# ZS-007.net
KiCad netlist of a schematic drawn in Altium Designer
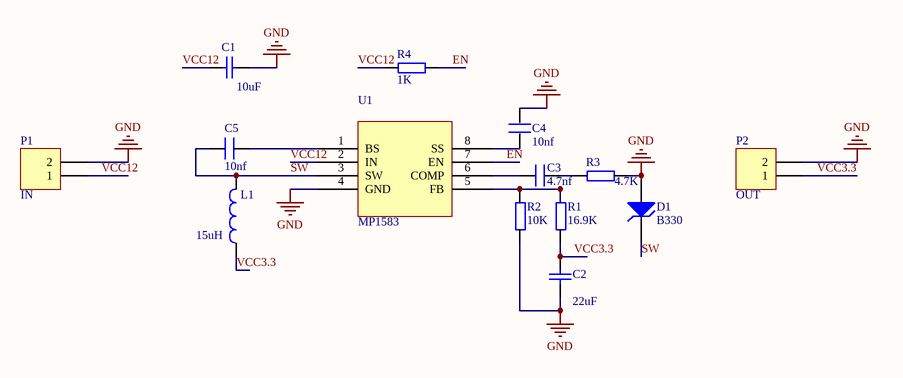
[diagram p0: ZS-007.SchDoc]

(export (version "E")
  (design (tool "Eeschema 10.0.6"))
  (components
    (comp (ref "C1")
      (value "10uF")
      (footprint "c0805")
      (description "Capacitor")
      (fields (field (name "Comment") "Cap") (field (name "PUBLISHER") "Altium Limited"))
      (libsource (lib "neoxin") (part "Cap0805"))
    )
    (comp (ref "C2")
      (value "22uF")
      (footprint "C0805")
      (description "Capacitor")
      (fields (field (name "Comment") "Cap") (field (name "PUBLISHER") "Altium Limited"))
      (libsource (lib "neoxin") (part "Cap0805"))
    )
    (comp (ref "C3") (value "4.7nf") (footprint "C0603") (libsource (lib "neoxin") (part "C")))
    (comp (ref "C4") (value "10nf") (footprint "C0603") (libsource (lib "neoxin") (part "C")))
    (comp (ref "C5") (value "10nf") (footprint "C0603") (libsource (lib "neoxin") (part "C")))
    (comp (ref "D1")
      (value "B330")
      (footprint "smb do214aa")
      (description "Zener Diode")
      (fields (field (name "PUBLISHER") "Altium Limited"))
      (libsource (lib "neoxin") (part "D Zener"))
    )
    (comp (ref "L1")
      (value "15uH")
      (footprint "15uh")
      (description "Inductor")
      (fields (field (name "PUBLISHER") "Altium Limited"))
      (libsource (lib "neoxin") (part "Inductor"))
    )
    (comp (ref "P1")
      (value "IN")
      (footprint "HDR1X2")
      (description "Header, 2-Pin")
      (fields (field (name "PUBLISHER") "Altium Limited"))
      (libsource (lib "Miscellaneous Connectors") (part "Header 2"))
    )
    (comp (ref "P2")
      (value "OUT")
      (footprint "HDR1X2")
      (description "Header, 2-Pin")
      (fields (field (name "PUBLISHER") "Altium Limited"))
      (libsource (lib "Miscellaneous Connectors") (part "Header 2"))
    )
    (comp (ref "R1") (value "16.9K") (footprint "R0603") (libsource (lib "neoxin") (part "R")))
    (comp (ref "R2") (value "10K") (footprint "R0603") (libsource (lib "neoxin") (part "R")))
    (comp (ref "R3") (value "4.7K") (footprint "R0603") (libsource (lib "neoxin") (part "R")))
    (comp (ref "R4") (value "1K") (footprint "R0603") (libsource (lib "neoxin") (part "R")))
    (comp (ref "U1")
      (value "MP1583")
      (footprint "SOP8")
      (description "DC-DC Step-Down Converter")
      (libsource (lib "neoxin") (part "MP1583"))
    )
  )
  (nets
    (net (code "1") (name "/EN") (class "Default")
      (node (ref "R4") (pin "2") (pintype "passive"))
      (node (ref "U1") (pin "7") (pinfunction "EN_7") (pintype "passive"))
    )
    (net (code "2") (name "/SW") (class "Default")
      (node (ref "C5") (pin "1") (pintype "passive"))
      (node (ref "D1") (pin "2") (pinfunction "K_2") (pintype "passive"))
      (node (ref "L1") (pin "2") (pinfunction "2_2") (pintype "passive"))
      (node (ref "U1") (pin "3") (pinfunction "SW_3") (pintype "passive"))
    )
    (net (code "3") (name "/VCC3.3") (class "Default")
      (node (ref "C2") (pin "1") (pinfunction "1_1") (pintype "passive"))
      (node (ref "L1") (pin "1") (pinfunction "1_1") (pintype "passive"))
      (node (ref "P2") (pin "1") (pinfunction "1_1") (pintype "passive"))
      (node (ref "R1") (pin "1") (pintype "passive"))
    )
    (net (code "4") (name "/VCC12") (class "Default")
      (node (ref "C1") (pin "1") (pinfunction "1_1") (pintype "passive"))
      (node (ref "P1") (pin "1") (pinfunction "1_1") (pintype "passive"))
      (node (ref "R4") (pin "1") (pintype "passive"))
      (node (ref "U1") (pin "2") (pinfunction "IN_2") (pintype "passive"))
    )
    (net (code "5") (name "GND") (class "Default")
      (node (ref "C1") (pin "2") (pinfunction "2_2") (pintype "passive"))
      (node (ref "C2") (pin "2") (pinfunction "2_2") (pintype "passive"))
      (node (ref "C4") (pin "2") (pintype "passive"))
      (node (ref "D1") (pin "1") (pinfunction "A_1") (pintype "passive"))
      (node (ref "P1") (pin "2") (pinfunction "2_2") (pintype "passive"))
      (node (ref "P2") (pin "2") (pinfunction "2_2") (pintype "passive"))
      (node (ref "R2") (pin "1") (pintype "passive"))
      (node (ref "R3") (pin "2") (pintype "passive"))
      (node (ref "U1") (pin "4") (pinfunction "GND_4") (pintype "passive"))
    )
    (net (code "6") (name "Net-(C3-Pad2)") (class "Default")
      (node (ref "C3") (pin "2") (pintype "passive"))
      (node (ref "R3") (pin "1") (pintype "passive"))
    )
    (net (code "7") (name "Net-(U1-BS)") (class "Default")
      (node (ref "C5") (pin "2") (pintype "passive"))
      (node (ref "U1") (pin "1") (pinfunction "BS_1") (pintype "passive"))
    )
    (net (code "8") (name "Net-(U1-COMP)") (class "Default")
      (node (ref "C3") (pin "1") (pintype "passive"))
      (node (ref "U1") (pin "6") (pinfunction "COMP_6") (pintype "passive"))
    )
    (net (code "9") (name "Net-(U1-FB)") (class "Default")
      (node (ref "R1") (pin "2") (pintype "passive"))
      (node (ref "R2") (pin "2") (pintype "passive"))
      (node (ref "U1") (pin "5") (pinfunction "FB_5") (pintype "passive"))
    )
    (net (code "10") (name "Net-(U1-SS)") (class "Default")
      (node (ref "C4") (pin "1") (pintype "passive"))
      (node (ref "U1") (pin "8") (pinfunction "SS_8") (pintype "passive"))
    )
  )
)
